# controller_rev2.net
KiCad netlist of a schematic drawn in EAGLE
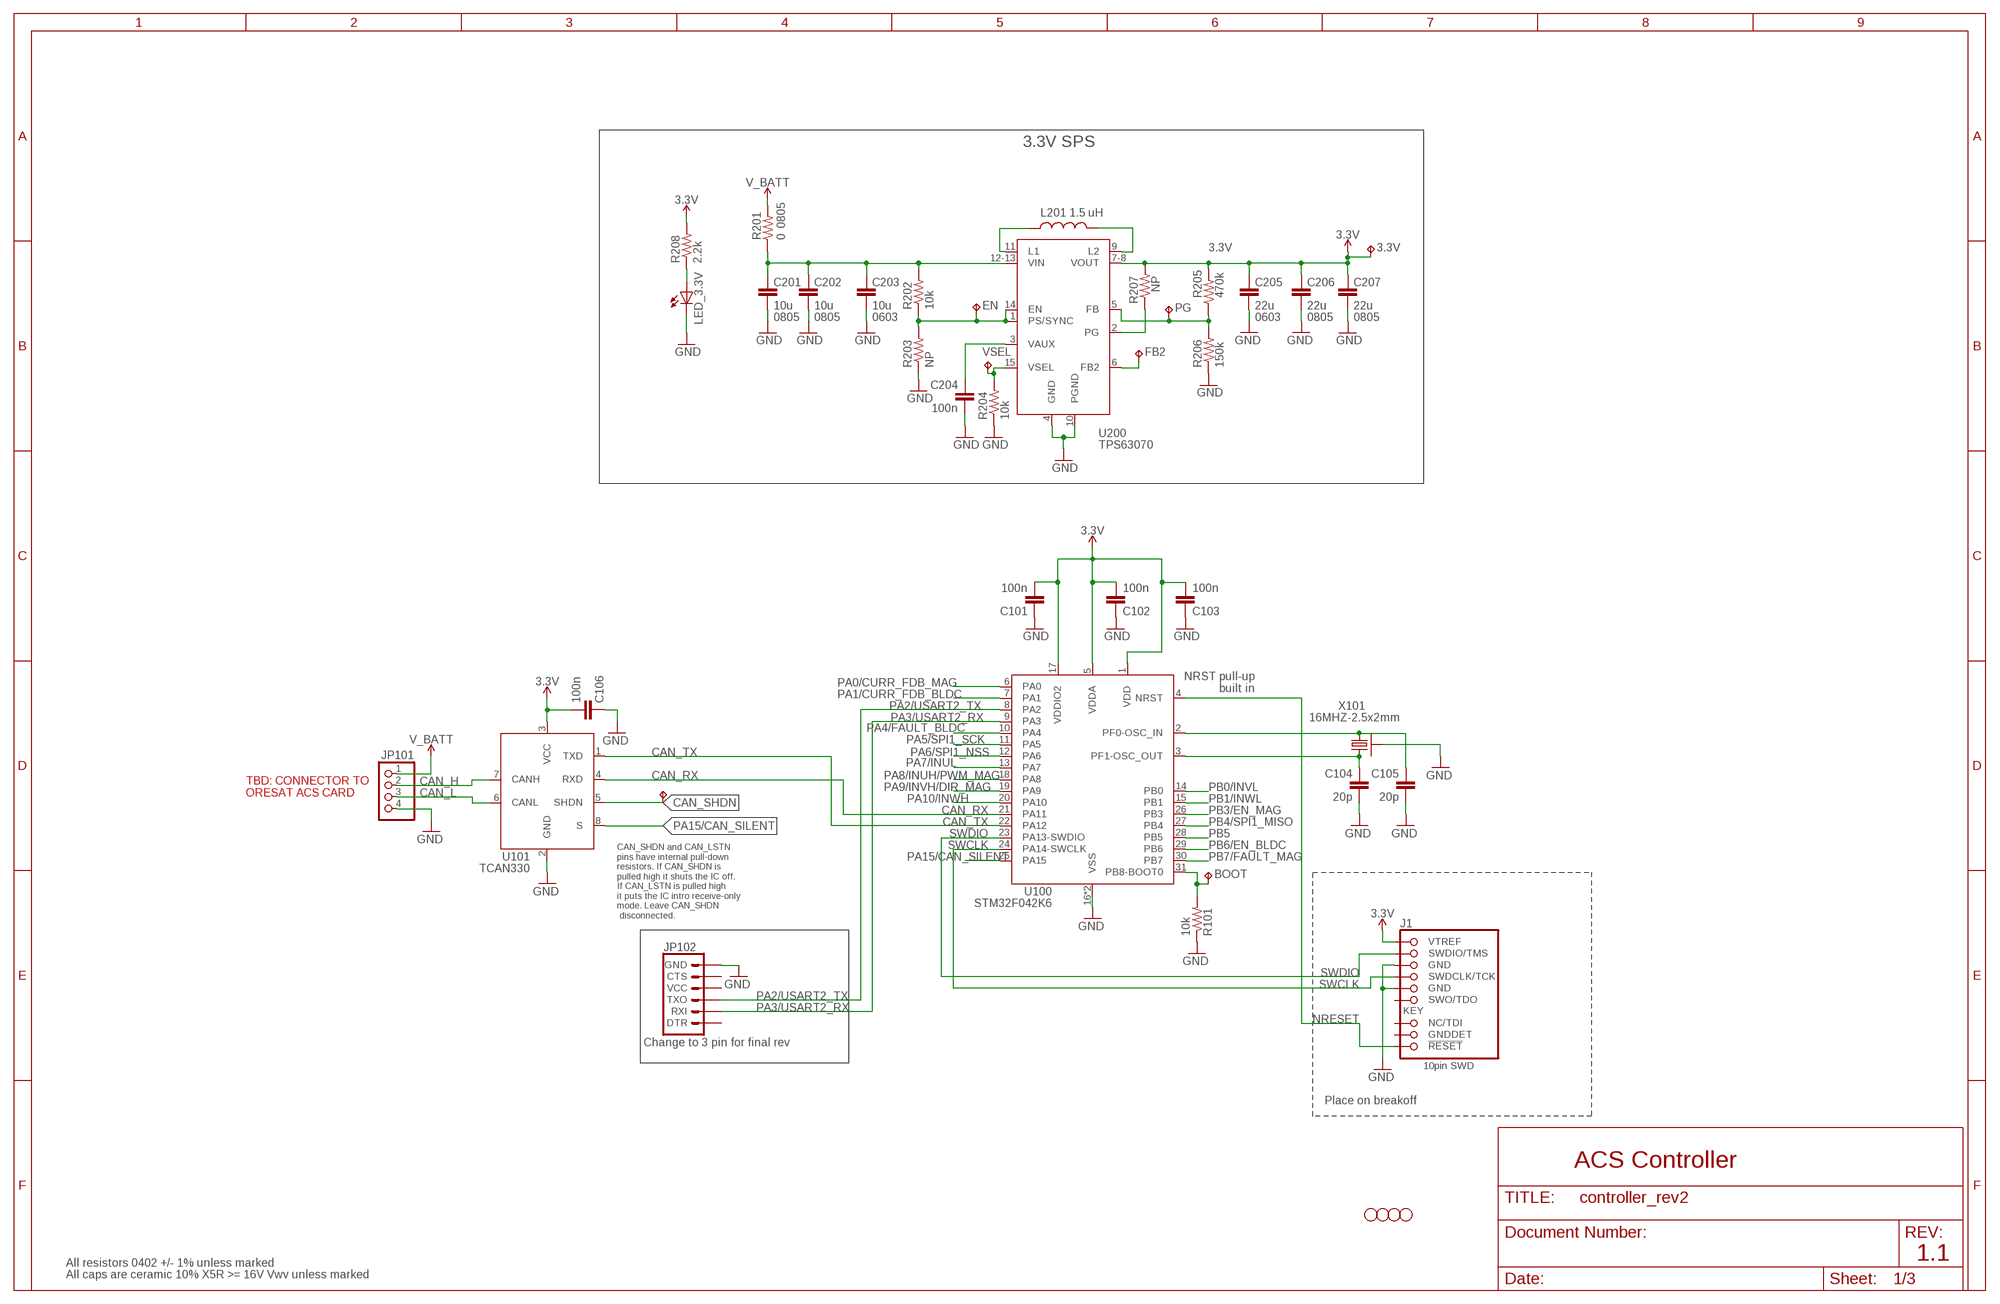
[diagram p0: schematic, sheet 1]
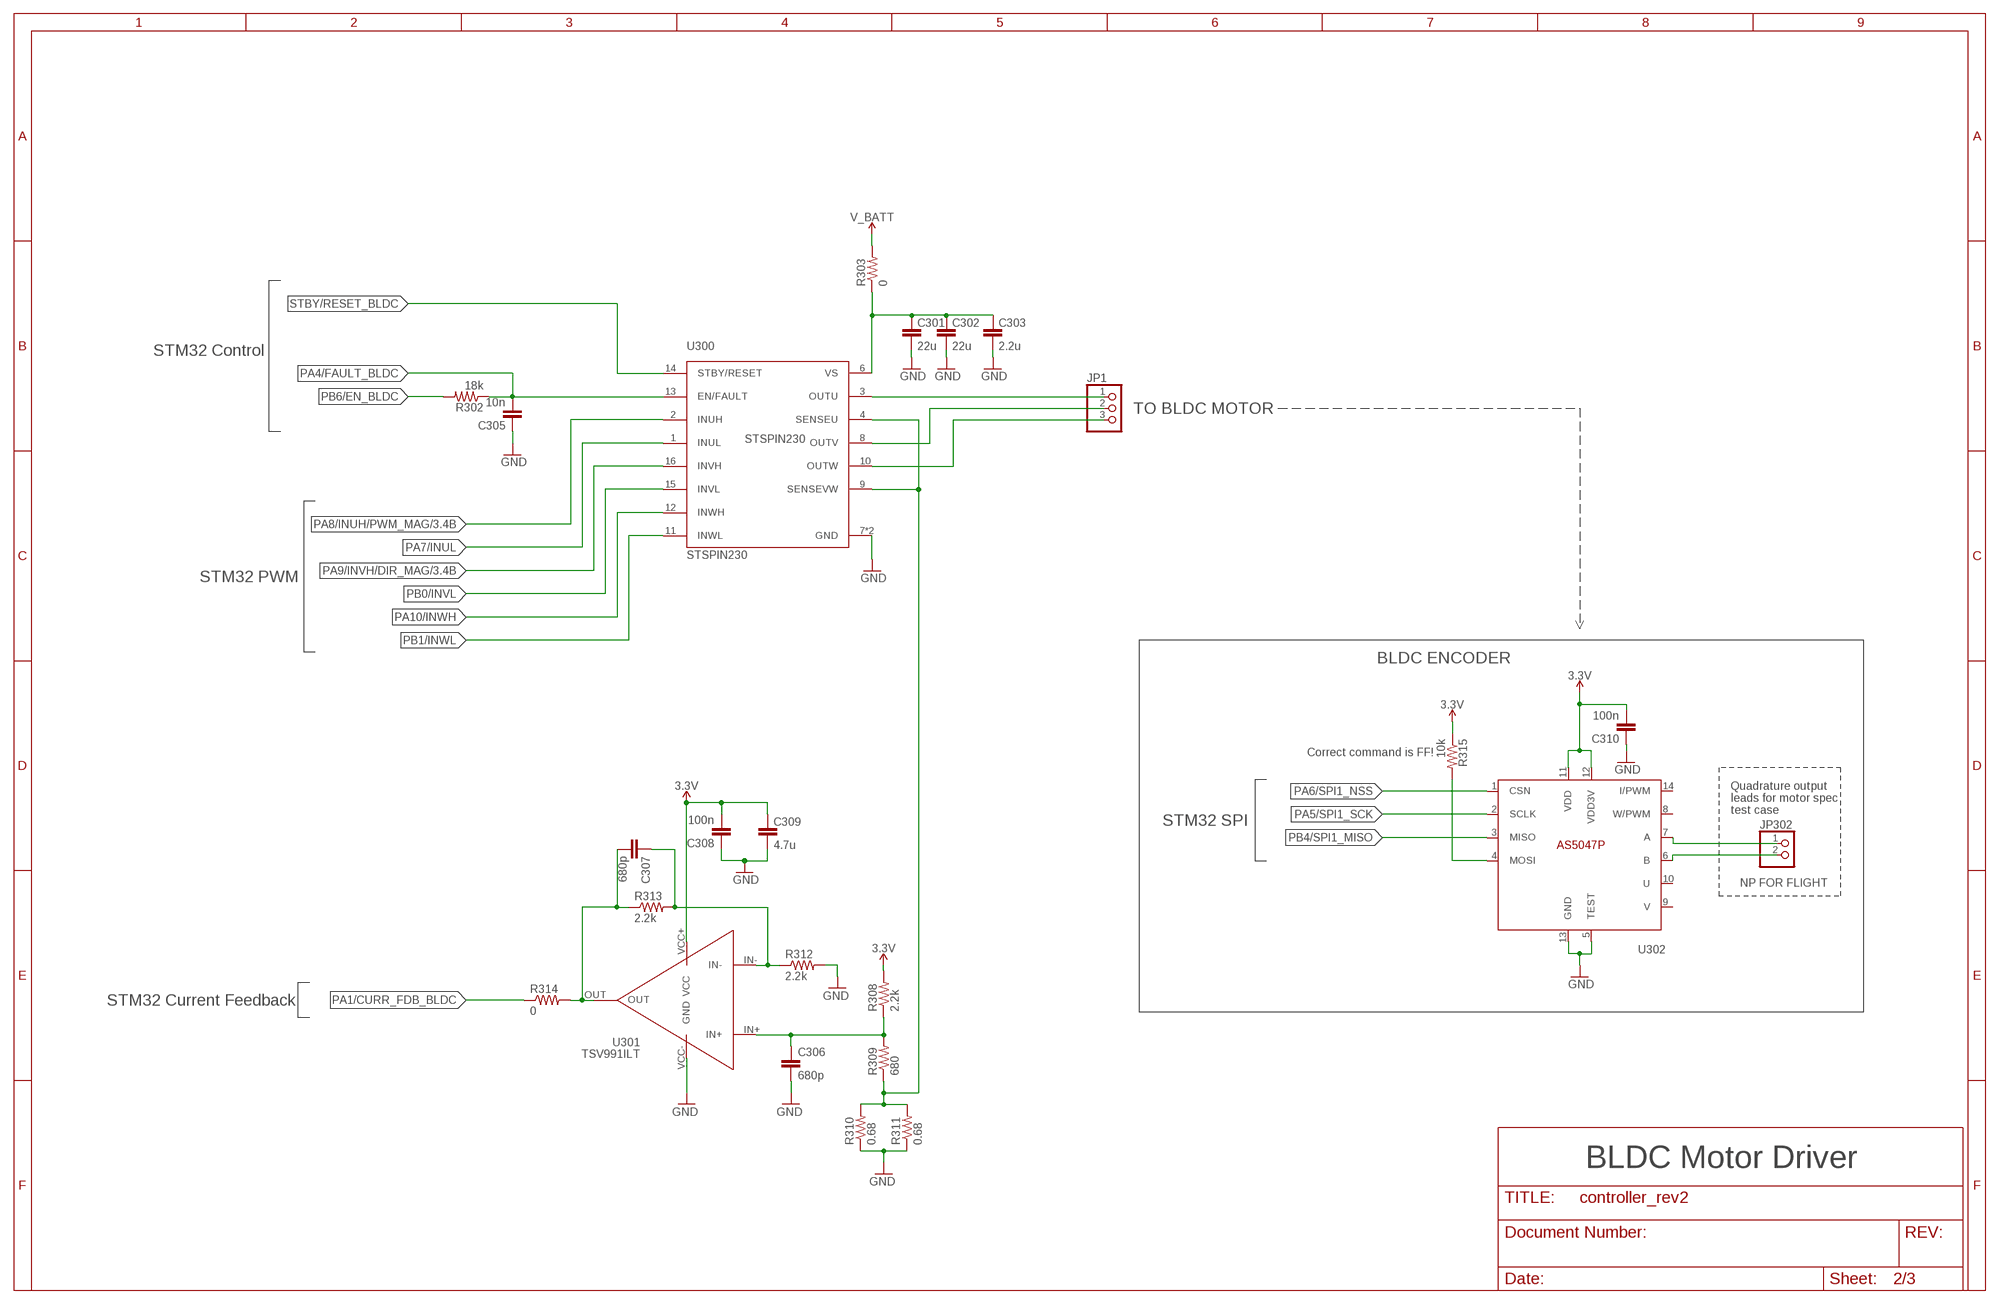
[diagram p1: schematic, sheet 2]
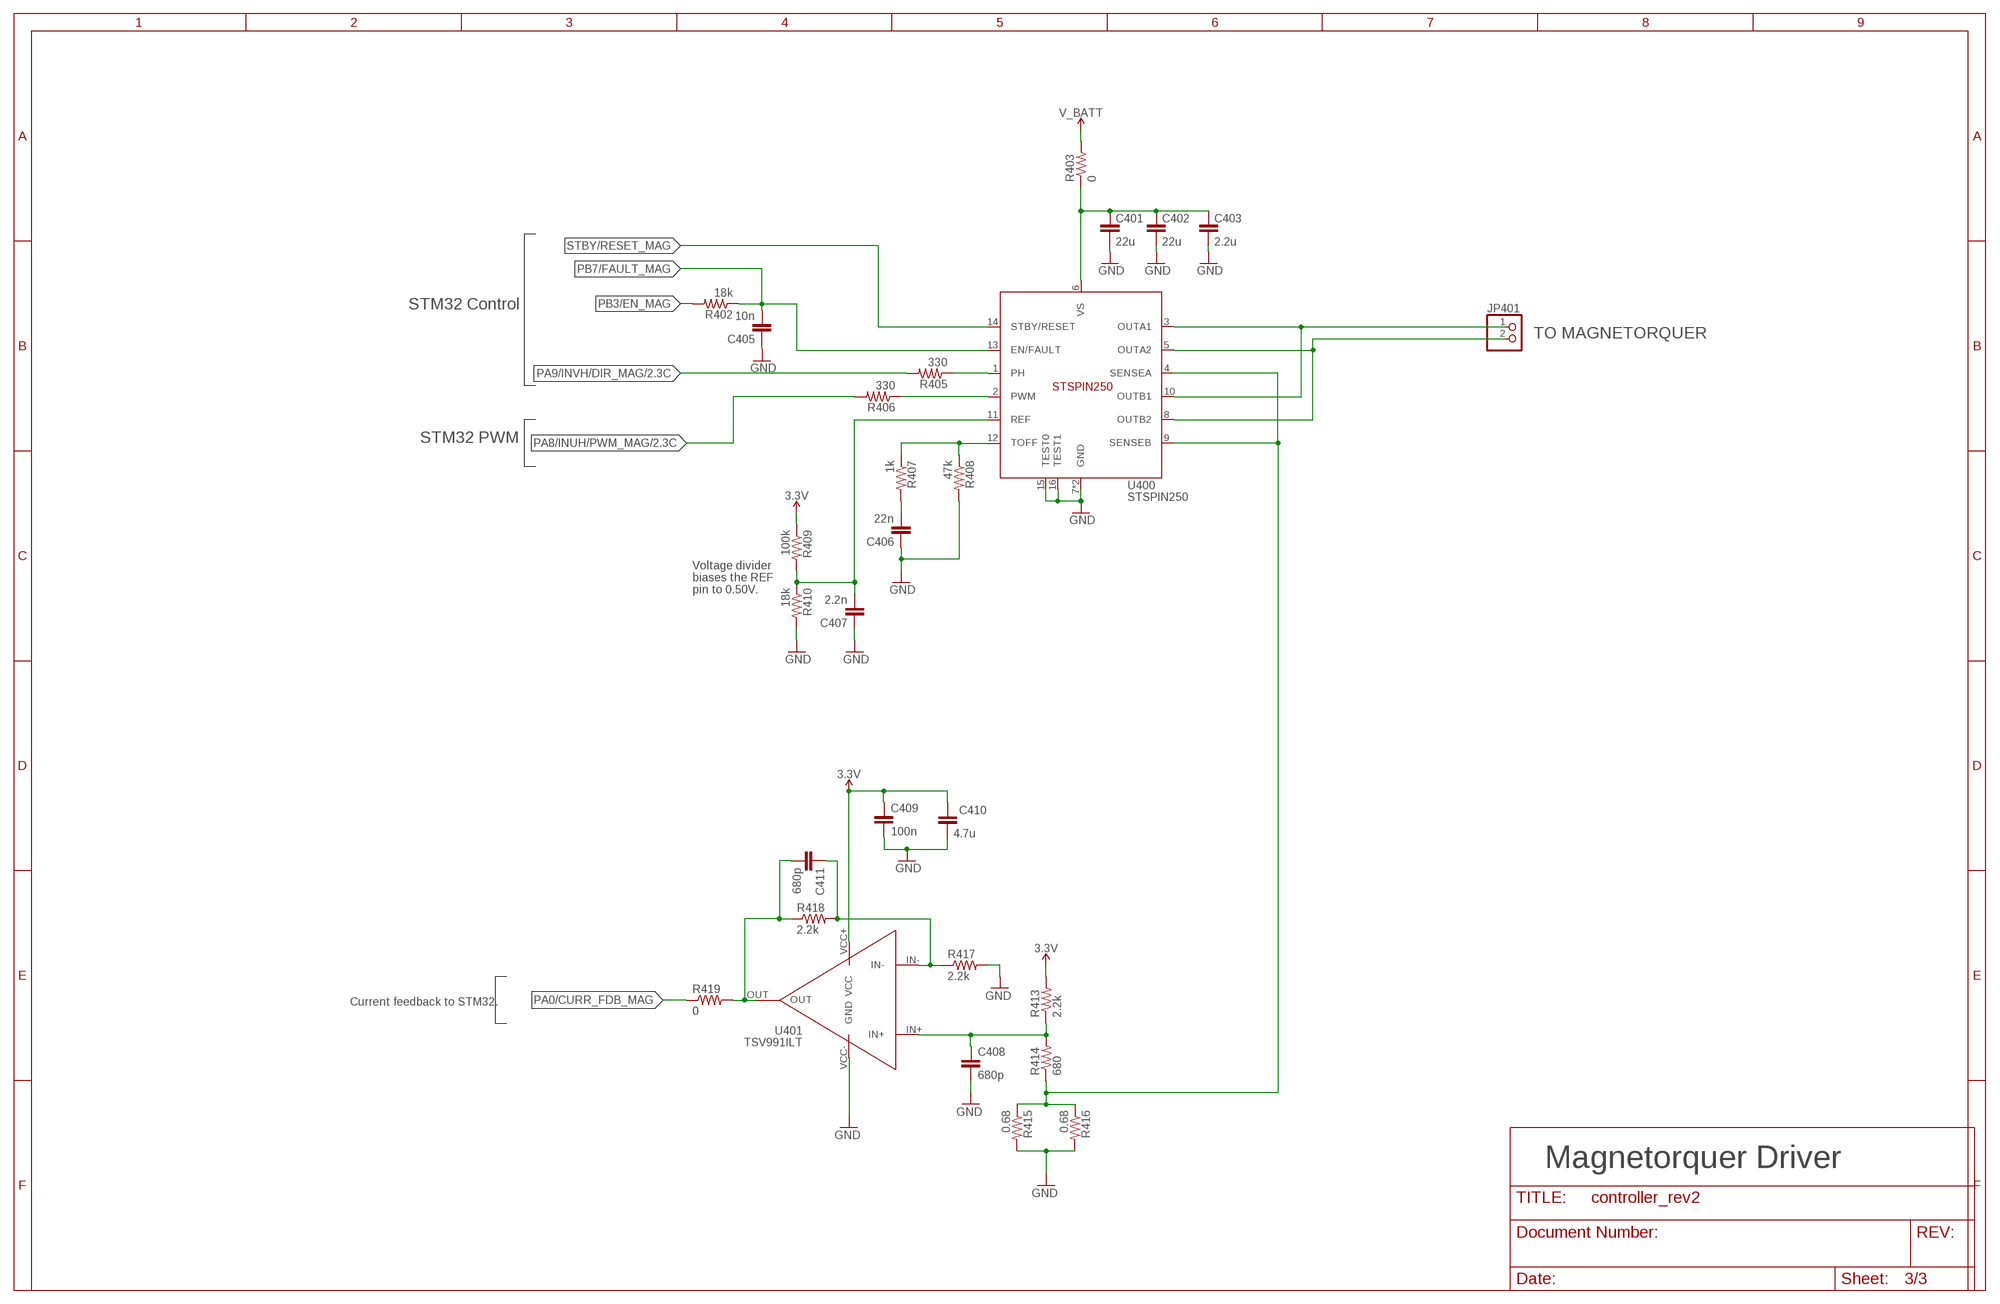
[diagram p2: schematic, sheet 3]

(export (version "E")
  (design (tool "Eeschema 10.0.6"))
  (components
    (comp (ref "C301")
      (value "22u")
      (footprint "eagle-import:.0603-B-NOSILK")
      (fields (field (name "MFR") "Samsung") (field (name "MPN") "CL05B104KO5NNNC"))
      (libsource (lib "eagle-import") (part "C-EU0603-B-NOSILK"))
    )
    (comp (ref "C302")
      (value "22u")
      (footprint "eagle-import:.0603-B-NOSILK")
      (fields (field (name "MFR") "Samsung") (field (name "MPN") "CL05B104KO5NNNC"))
      (libsource (lib "eagle-import") (part "C-EU0603-B-NOSILK"))
    )
    (comp (ref "C303")
      (value "2.2u")
      (footprint "eagle-import:.0603-B-NOSILK")
      (fields (field (name "MFR") "Samsung") (field (name "MPN") "CL05B104KO5NNNC"))
      (libsource (lib "eagle-import") (part "C-EU0603-B-NOSILK"))
    )
    (comp (ref "C305")
      (value "10n")
      (footprint "eagle-import:.0402-B-NOSILK")
      (fields (field (name "MFR") "Samsung") (field (name "MPN") "CL05B104KO5NNNC"))
      (libsource (lib "eagle-import") (part "rcl_custom_C-EU0402-B-NOSILK"))
    )
    (comp (ref "C306")
      (value "680p")
      (footprint "eagle-import:.0402-B-NOSILK")
      (fields (field (name "MFR") "Samsung") (field (name "MPN") "CL05B104KO5NNNC"))
      (libsource (lib "eagle-import") (part "rcl_custom_C-EU0402-B-NOSILK"))
    )
    (comp (ref "C307")
      (value "680p")
      (footprint "eagle-import:.0402-B-NOSILK")
      (fields (field (name "MFR") "Samsung") (field (name "MPN") "CL05B104KO5NNNC"))
      (libsource (lib "eagle-import") (part "rcl_custom_C-EU0402-B-NOSILK"))
    )
    (comp (ref "C308")
      (value "100n")
      (footprint "eagle-import:.0402-B-NOSILK")
      (fields (field (name "MFR") "Samsung") (field (name "MPN") "CL05B104KO5NNNC"))
      (libsource (lib "eagle-import") (part "rcl_custom_C-EU0402-B-NOSILK"))
    )
    (comp (ref "C309")
      (value "4.7u")
      (footprint "eagle-import:.0603-B-NOSILK")
      (fields (field (name "MFR") "Samsung") (field (name "MPN") "CL05B104KO5NNNC"))
      (libsource (lib "eagle-import") (part "C-EU0603-B-NOSILK"))
    )
    (comp (ref "C310")
      (value "100n")
      (footprint "eagle-import:.0402-B-NOSILK")
      (fields (field (name "MFR") "Samsung") (field (name "MPN") "CL05B104KO5NNNC"))
      (libsource (lib "eagle-import") (part "rcl_custom_C-EU0402-B-NOSILK"))
    )
    (comp (ref "JP1")
      (value "PINHD-1X3")
      (footprint "eagle-import:1X03")
      (libsource (lib "eagle-import") (part "PINHD-1X3"))
    )
    (comp (ref "JP302")
      (value "PINHD-1X2")
      (footprint "eagle-import:1X02")
      (libsource (lib "eagle-import") (part "PINHD-1X2"))
    )
    (comp (ref "R302")
      (value "18k")
      (footprint "eagle-import:.0402-B-NOSILK")
      (fields (field (name "MFR") "Samsung") (field (name "MPN") "RC1005F6653CS"))
      (libsource (lib "eagle-import") (part "rcl_custom_R-US_0402-B-NOSILK"))
    )
    (comp (ref "R303")
      (value "0")
      (footprint "eagle-import:.0805-B-NOSILK")
      (libsource (lib "eagle-import") (part "R-US_0805-B-NOSILK"))
    )
    (comp (ref "R308")
      (value "2.2k")
      (footprint "eagle-import:.0402-B-NOSILK")
      (fields (field (name "MFR") "Samsung") (field (name "MPN") "RC1005F6653CS"))
      (libsource (lib "eagle-import") (part "rcl_custom_R-US_0402-B-NOSILK"))
    )
    (comp (ref "R309")
      (value "680")
      (footprint "eagle-import:.0402-B-NOSILK")
      (fields (field (name "MFR") "Samsung") (field (name "MPN") "RC1005F6653CS"))
      (libsource (lib "eagle-import") (part "rcl_custom_R-US_0402-B-NOSILK"))
    )
    (comp (ref "R310")
      (value "0.68")
      (footprint "eagle-import:.0805-B-NOSILK")
      (libsource (lib "eagle-import") (part "R-US_0805-B-NOSILK"))
    )
    (comp (ref "R311")
      (value "0.68")
      (footprint "eagle-import:.0805-B-NOSILK")
      (libsource (lib "eagle-import") (part "R-US_0805-B-NOSILK"))
    )
    (comp (ref "R312")
      (value "2.2k")
      (footprint "eagle-import:.0402-B-NOSILK")
      (fields (field (name "MFR") "Samsung") (field (name "MPN") "RC1005F6653CS"))
      (libsource (lib "eagle-import") (part "rcl_custom_R-US_0402-B-NOSILK"))
    )
    (comp (ref "R313")
      (value "2.2k")
      (footprint "eagle-import:.0402-B-NOSILK")
      (fields (field (name "MFR") "Samsung") (field (name "MPN") "RC1005F6653CS"))
      (libsource (lib "eagle-import") (part "rcl_custom_R-US_0402-B-NOSILK"))
    )
    (comp (ref "R314")
      (value "0")
      (footprint "eagle-import:.0402-B-NOSILK")
      (fields (field (name "MFR") "Samsung") (field (name "MPN") "RC1005F6653CS"))
      (libsource (lib "eagle-import") (part "rcl_custom_R-US_0402-B-NOSILK"))
    )
    (comp (ref "R315")
      (value "10k")
      (footprint "eagle-import:.0402-B-NOSILK")
      (fields (field (name "MFR") "Samsung") (field (name "MPN") "RC1005F6653CS"))
      (libsource (lib "eagle-import") (part "rcl_custom_R-US_0402-B-NOSILK"))
    )
    (comp (ref "U300")
      (value "STSPIN230")
      (footprint "eagle-import:VFQFPN")
      (libsource (lib "eagle-import") (part "STSPIN230"))
    )
    (comp (ref "U301")
      (value "TSV991ILT")
      (footprint "eagle-import:SOT23-5")
      (libsource (lib "eagle-import") (part "TSV991ILT"))
    )
    (comp (ref "U302")
      (value "AS5047P")
      (footprint "eagle-import:TSSOP14")
      (libsource (lib "eagle-import") (part "AS5047P"))
    )
    (comp (ref "3.3V")
      (value "TPTP15SQ")
      (footprint "eagle-import:TP15SQ")
      (libsource (lib "eagle-import") (part "TPTP15SQ"))
    )
    (comp (ref "BOOT")
      (value "TPTP15SQ")
      (footprint "eagle-import:TP15SQ")
      (libsource (lib "eagle-import") (part "TPTP15SQ"))
    )
    (comp (ref "BOOT1")
      (value "TPTP15SQ")
      (footprint "eagle-import:TP15SQ")
      (libsource (lib "eagle-import") (part "TPTP15SQ"))
    )
    (comp (ref "C101")
      (value "100n")
      (footprint "eagle-import:.0402-B-NOSILK")
      (fields (field (name "MFR") "Samsung") (field (name "MPN") "CL05B104KO5NNNC"))
      (libsource (lib "eagle-import") (part "rcl_custom_C-EU0402-B-NOSILK"))
    )
    (comp (ref "C102")
      (value "100n")
      (footprint "eagle-import:.0402-B-NOSILK")
      (fields (field (name "MFR") "Samsung") (field (name "MPN") "CL05B104KO5NNNC"))
      (libsource (lib "eagle-import") (part "rcl_custom_C-EU0402-B-NOSILK"))
    )
    (comp (ref "C103")
      (value "100n")
      (footprint "eagle-import:.0402-B-NOSILK")
      (fields (field (name "MFR") "Samsung") (field (name "MPN") "CL05B104KO5NNNC"))
      (libsource (lib "eagle-import") (part "rcl_custom_C-EU0402-B-NOSILK"))
    )
    (comp (ref "C104")
      (value "20p")
      (footprint "eagle-import:.0402-B-NOSILK")
      (fields (field (name "MFR") "Samsung") (field (name "MPN") "CL05C200JB51PNC"))
      (libsource (lib "eagle-import") (part "rcl_custom_C-EU0402-B-NOSILK"))
    )
    (comp (ref "C105")
      (value "20p")
      (footprint "eagle-import:.0402-B-NOSILK")
      (fields (field (name "MFR") "Samsung") (field (name "MPN") "CL05C200JB51PNC"))
      (libsource (lib "eagle-import") (part "rcl_custom_C-EU0402-B-NOSILK"))
    )
    (comp (ref "C106")
      (value "100n")
      (footprint "eagle-import:.0402-B-NOSILK")
      (fields (field (name "MFR") "Samsung") (field (name "MPN") "CL05B104KO5NNNC"))
      (libsource (lib "eagle-import") (part "rcl_custom_C-EU0402-B-NOSILK"))
    )
    (comp (ref "C201")
      (value "10u")
      (footprint "eagle-import:.0805-B-NOSILK")
      (libsource (lib "eagle-import") (part "C-EU0805-B-NOSILK"))
    )
    (comp (ref "C202")
      (value "10u")
      (footprint "eagle-import:.0805-B-NOSILK")
      (libsource (lib "eagle-import") (part "C-EU0805-B-NOSILK"))
    )
    (comp (ref "C203")
      (value "10u")
      (footprint "eagle-import:.0603-B-NOSILK")
      (fields (field (name "MFR") "Samsung") (field (name "MPN") "CL05B104KO5NNNC"))
      (libsource (lib "eagle-import") (part "C-EU0603-B-NOSILK"))
    )
    (comp (ref "C204")
      (value "100n")
      (footprint "eagle-import:.0402-B-NOSILK")
      (fields (field (name "MFR") "Samsung") (field (name "MPN") "CL05B104KO5NNNC"))
      (libsource (lib "eagle-import") (part "rcl_custom_C-EU0402-B-NOSILK"))
    )
    (comp (ref "C205")
      (value "22u")
      (footprint "eagle-import:.0603-B-NOSILK")
      (fields (field (name "MFR") "Samsung") (field (name "MPN") "CL05B104KO5NNNC"))
      (libsource (lib "eagle-import") (part "C-EU0603-B-NOSILK"))
    )
    (comp (ref "C206")
      (value "22u")
      (footprint "eagle-import:.0805-B-NOSILK")
      (libsource (lib "eagle-import") (part "C-EU0805-B-NOSILK"))
    )
    (comp (ref "C207")
      (value "22u")
      (footprint "eagle-import:.0805-B-NOSILK")
      (libsource (lib "eagle-import") (part "C-EU0805-B-NOSILK"))
    )
    (comp (ref "EN")
      (value "TPTP15SQ")
      (footprint "eagle-import:TP15SQ")
      (libsource (lib "eagle-import") (part "TPTP15SQ"))
    )
    (comp (ref "FB2")
      (value "TPTP15SQ")
      (footprint "eagle-import:TP15SQ")
      (libsource (lib "eagle-import") (part "TPTP15SQ"))
    )
    (comp (ref "H1")
      (value "STAND-OFFTIGHT")
      (footprint "eagle-import:STAND-OFF-TIGHT")
      (libsource (lib "eagle-import") (part "STAND-OFFTIGHT"))
    )
    (comp (ref "H2")
      (value "STAND-OFFTIGHT")
      (footprint "eagle-import:STAND-OFF-TIGHT")
      (libsource (lib "eagle-import") (part "STAND-OFFTIGHT"))
    )
    (comp (ref "H3")
      (value "STAND-OFFTIGHT")
      (footprint "eagle-import:STAND-OFF-TIGHT")
      (libsource (lib "eagle-import") (part "STAND-OFFTIGHT"))
    )
    (comp (ref "H4")
      (value "STAND-OFFTIGHT")
      (footprint "eagle-import:STAND-OFF-TIGHT")
      (libsource (lib "eagle-import") (part "STAND-OFFTIGHT"))
    )
    (comp (ref "J1")
      (value "1.27MM-SWD-CONNECTOR")
      (footprint "eagle-import:1.27MM_2X5")
      (libsource (lib "eagle-import") (part "1.27MM-SWD-CONNECTOR"))
    )
    (comp (ref "JP101")
      (value "PINHD-1X4")
      (footprint "eagle-import:1X04")
      (libsource (lib "eagle-import") (part "PINHD-1X4"))
    )
    (comp (ref "JP102")
      (value "6_PIN_SERIAL_TARGETSILK")
      (footprint "eagle-import:6_PIN_SERIAL_TARGET_SIDE_W_SILK")
      (libsource (lib "eagle-import") (part "6_PIN_SERIAL_TARGETSILK"))
    )
    (comp (ref "L201")
      (value "1.5 uH")
      (footprint "eagle-import:L-COILCRAFT-XFL4020")
      (fields (field (name "MFR") "Coilcraft") (field (name "MPN") "XFL4020-152ME"))
      (libsource (lib "eagle-import") (part "L-COILCRAFT-XFL4020"))
    )
    (comp (ref "LED_3.3V")
      (value "LEDCHIPLED_0603")
      (footprint "eagle-import:CHIPLED_0603")
      (libsource (lib "eagle-import") (part "LEDCHIPLED_0603"))
    )
    (comp (ref "PG")
      (value "TPTP15SQ")
      (footprint "eagle-import:TP15SQ")
      (libsource (lib "eagle-import") (part "TPTP15SQ"))
    )
    (comp (ref "R101")
      (value "10k")
      (footprint "eagle-import:.0402-B-NOSILK")
      (fields (field (name "MFR") "Samsung") (field (name "MPN") "RC1005F6653CS"))
      (libsource (lib "eagle-import") (part "rcl_custom_R-US_0402-B-NOSILK"))
    )
    (comp (ref "R201")
      (value "0")
      (footprint "eagle-import:.0805-B-NOSILK")
      (fields (field (name "MFR") "Rohm") (field (name "MPN") "MCR10EZPJ000"))
      (libsource (lib "eagle-import") (part "rcl_custom_R-US_0805-B-NOSILK"))
    )
    (comp (ref "R202")
      (value "10k")
      (footprint "eagle-import:.0402-B-NOSILK")
      (fields (field (name "MFR") "Samsung") (field (name "MPN") "RC1005F6653CS"))
      (libsource (lib "eagle-import") (part "rcl_custom_R-US_0402-B-NOSILK"))
    )
    (comp (ref "R203")
      (value "NP")
      (footprint "eagle-import:.0402-B-NOSILK")
      (fields (field (name "MFR") "Samsung") (field (name "MPN") "RC1005F6653CS"))
      (libsource (lib "eagle-import") (part "rcl_custom_R-US_0402-B-NOSILK"))
    )
    (comp (ref "R204")
      (value "10k")
      (footprint "eagle-import:.0402-B-NOSILK")
      (fields (field (name "MFR") "Samsung") (field (name "MPN") "RC1005F6653CS"))
      (libsource (lib "eagle-import") (part "rcl_custom_R-US_0402-B-NOSILK"))
    )
    (comp (ref "R205")
      (value "470k")
      (footprint "eagle-import:.0402-B-NOSILK")
      (fields (field (name "MFR") "Samsung") (field (name "MPN") "RC1005F6653CS"))
      (libsource (lib "eagle-import") (part "rcl_custom_R-US_0402-B-NOSILK"))
    )
    (comp (ref "R206")
      (value "150k")
      (footprint "eagle-import:.0402-B-NOSILK")
      (fields (field (name "MFR") "Samsung") (field (name "MPN") "RC1005F6653CS"))
      (libsource (lib "eagle-import") (part "rcl_custom_R-US_0402-B-NOSILK"))
    )
    (comp (ref "R207")
      (value "NP")
      (footprint "eagle-import:.0402-B-NOSILK")
      (fields (field (name "MFR") "Samsung") (field (name "MPN") "RC1005F6653CS"))
      (libsource (lib "eagle-import") (part "rcl_custom_R-US_0402-B-NOSILK"))
    )
    (comp (ref "R208")
      (value "2.2k")
      (footprint "eagle-import:.0603-B-NOSILK")
      (libsource (lib "eagle-import") (part "R-US_0603-B-NOSILK"))
    )
    (comp (ref "U100")
      (value "STM32F042K6")
      (footprint "eagle-import:QFP32-7X7")
      (fields (field (name "MFR") "STMicroelectronics") (field (name "MPN") "STM32F042K6T7"))
      (libsource (lib "eagle-import") (part "STM32F042K6"))
    )
    (comp (ref "U101")
      (value "TCAN330")
      (footprint "eagle-import:SOT23-8_TI-DCN")
      (fields (field (name "MFR") "Texas Instruments") (field (name "MPN") "TCAN330GDCNT"))
      (libsource (lib "eagle-import") (part "TCAN330"))
    )
    (comp (ref "U200")
      (value "TPS63070")
      (footprint "eagle-import:TPS63070X")
      (libsource (lib "eagle-import") (part "TPS63070X"))
    )
    (comp (ref "VSEL")
      (value "TPTP15SQ")
      (footprint "eagle-import:TP15SQ")
      (libsource (lib "eagle-import") (part "TPTP15SQ"))
    )
    (comp (ref "X101")
      (value "16MHZ-2.5x2mm")
      (footprint "eagle-import:CRYSTAL_2.5X2")
      (fields (field (name "MFR") "ECS Inc.") (field (name "MPN") "ECS-160-10-36Q-ES-TR"))
      (libsource (lib "eagle-import") (part "CRYSTAL-WITH-GND"))
    )
    (comp (ref "C401")
      (value "22u")
      (footprint "eagle-import:.0603-B-NOSILK")
      (fields (field (name "MFR") "Samsung") (field (name "MPN") "CL05B104KO5NNNC"))
      (libsource (lib "eagle-import") (part "C-EU0603-B-NOSILK"))
    )
    (comp (ref "C402")
      (value "22u")
      (footprint "eagle-import:.0603-B-NOSILK")
      (fields (field (name "MFR") "Samsung") (field (name "MPN") "CL05B104KO5NNNC"))
      (libsource (lib "eagle-import") (part "C-EU0603-B-NOSILK"))
    )
    (comp (ref "C403")
      (value "2.2u")
      (footprint "eagle-import:.0603-B-NOSILK")
      (fields (field (name "MFR") "Samsung") (field (name "MPN") "CL05B104KO5NNNC"))
      (libsource (lib "eagle-import") (part "C-EU0603-B-NOSILK"))
    )
    (comp (ref "C405")
      (value "10n")
      (footprint "eagle-import:.0402-B-NOSILK")
      (fields (field (name "MFR") "Samsung") (field (name "MPN") "CL05B104KO5NNNC"))
      (libsource (lib "eagle-import") (part "rcl_custom_C-EU0402-B-NOSILK"))
    )
    (comp (ref "C406")
      (value "22n")
      (footprint "eagle-import:.0402-B-NOSILK")
      (fields (field (name "MFR") "Samsung") (field (name "MPN") "CL05B104KO5NNNC"))
      (libsource (lib "eagle-import") (part "rcl_custom_C-EU0402-B-NOSILK"))
    )
    (comp (ref "C407")
      (value "2.2n")
      (footprint "eagle-import:.0402-B-NOSILK")
      (fields (field (name "MFR") "Samsung") (field (name "MPN") "CL05B104KO5NNNC"))
      (libsource (lib "eagle-import") (part "rcl_custom_C-EU0402-B-NOSILK"))
    )
    (comp (ref "C408")
      (value "680p")
      (footprint "eagle-import:.0402-B-NOSILK")
      (fields (field (name "MFR") "Samsung") (field (name "MPN") "CL05B104KO5NNNC"))
      (libsource (lib "eagle-import") (part "rcl_custom_C-EU0402-B-NOSILK"))
    )
    (comp (ref "C409")
      (value "100n")
      (footprint "eagle-import:.0402-B-NOSILK")
      (fields (field (name "MFR") "Samsung") (field (name "MPN") "CL05B104KO5NNNC"))
      (libsource (lib "eagle-import") (part "rcl_custom_C-EU0402-B-NOSILK"))
    )
    (comp (ref "C410")
      (value "4.7u")
      (footprint "eagle-import:.0603-B-NOSILK")
      (fields (field (name "MFR") "Samsung") (field (name "MPN") "CL05B104KO5NNNC"))
      (libsource (lib "eagle-import") (part "C-EU0603-B-NOSILK"))
    )
    (comp (ref "C411")
      (value "680p")
      (footprint "eagle-import:.0402-B-NOSILK")
      (fields (field (name "MFR") "Samsung") (field (name "MPN") "CL05B104KO5NNNC"))
      (libsource (lib "eagle-import") (part "rcl_custom_C-EU0402-B-NOSILK"))
    )
    (comp (ref "JP401")
      (value "PINHD-1X2")
      (footprint "eagle-import:1X02")
      (libsource (lib "eagle-import") (part "PINHD-1X2"))
    )
    (comp (ref "R402")
      (value "18k")
      (footprint "eagle-import:.0402-B-NOSILK")
      (fields (field (name "MFR") "Samsung") (field (name "MPN") "RC1005F6653CS"))
      (libsource (lib "eagle-import") (part "rcl_custom_R-US_0402-B-NOSILK"))
    )
    (comp (ref "R403")
      (value "0")
      (footprint "eagle-import:.0805-B-NOSILK")
      (libsource (lib "eagle-import") (part "R-US_0805-B-NOSILK"))
    )
    (comp (ref "R405")
      (value "330")
      (footprint "eagle-import:.0402-B-NOSILK")
      (fields (field (name "MFR") "Samsung") (field (name "MPN") "RC1005F6653CS"))
      (libsource (lib "eagle-import") (part "rcl_custom_R-US_0402-B-NOSILK"))
    )
    (comp (ref "R406")
      (value "330")
      (footprint "eagle-import:.0402-B-NOSILK")
      (fields (field (name "MFR") "Samsung") (field (name "MPN") "RC1005F6653CS"))
      (libsource (lib "eagle-import") (part "rcl_custom_R-US_0402-B-NOSILK"))
    )
    (comp (ref "R407")
      (value "1k")
      (footprint "eagle-import:.0402-B-NOSILK")
      (fields (field (name "MFR") "Samsung") (field (name "MPN") "RC1005F6653CS"))
      (libsource (lib "eagle-import") (part "rcl_custom_R-US_0402-B-NOSILK"))
    )
    (comp (ref "R408")
      (value "47k")
      (footprint "eagle-import:.0402-B-NOSILK")
      (fields (field (name "MFR") "Samsung") (field (name "MPN") "RC1005F6653CS"))
      (libsource (lib "eagle-import") (part "rcl_custom_R-US_0402-B-NOSILK"))
    )
    (comp (ref "R409")
      (value "100k")
      (footprint "eagle-import:.0402-B-NOSILK")
      (fields (field (name "MFR") "Samsung") (field (name "MPN") "RC1005F6653CS"))
      (libsource (lib "eagle-import") (part "rcl_custom_R-US_0402-B-NOSILK"))
    )
    (comp (ref "R410")
      (value "18k")
      (footprint "eagle-import:.0402-B-NOSILK")
      (fields (field (name "MFR") "Samsung") (field (name "MPN") "RC1005F6653CS"))
      (libsource (lib "eagle-import") (part "rcl_custom_R-US_0402-B-NOSILK"))
    )
    (comp (ref "R413")
      (value "2.2k")
      (footprint "eagle-import:.0402-B-NOSILK")
      (fields (field (name "MFR") "Samsung") (field (name "MPN") "RC1005F6653CS"))
      (libsource (lib "eagle-import") (part "rcl_custom_R-US_0402-B-NOSILK"))
    )
    (comp (ref "R414")
      (value "680")
      (footprint "eagle-import:.0402-B-NOSILK")
      (fields (field (name "MFR") "Samsung") (field (name "MPN") "RC1005F6653CS"))
      (libsource (lib "eagle-import") (part "rcl_custom_R-US_0402-B-NOSILK"))
    )
    (comp (ref "R415")
      (value "0.68")
      (footprint "eagle-import:.0805-B-NOSILK")
      (libsource (lib "eagle-import") (part "R-US_0805-B-NOSILK"))
    )
    (comp (ref "R416")
      (value "0.68")
      (footprint "eagle-import:.0805-B-NOSILK")
      (libsource (lib "eagle-import") (part "R-US_0805-B-NOSILK"))
    )
    (comp (ref "R417")
      (value "2.2k")
      (footprint "eagle-import:.0402-B-NOSILK")
      (fields (field (name "MFR") "Samsung") (field (name "MPN") "RC1005F6653CS"))
      (libsource (lib "eagle-import") (part "rcl_custom_R-US_0402-B-NOSILK"))
    )
    (comp (ref "R418")
      (value "2.2k")
      (footprint "eagle-import:.0402-B-NOSILK")
      (fields (field (name "MFR") "Samsung") (field (name "MPN") "RC1005F6653CS"))
      (libsource (lib "eagle-import") (part "rcl_custom_R-US_0402-B-NOSILK"))
    )
    (comp (ref "R419")
      (value "0")
      (footprint "eagle-import:.0402-B-NOSILK")
      (fields (field (name "MFR") "Samsung") (field (name "MPN") "RC1005F6653CS"))
      (libsource (lib "eagle-import") (part "rcl_custom_R-US_0402-B-NOSILK"))
    )
    (comp (ref "U400")
      (value "STSPIN250")
      (footprint "eagle-import:VFQPN")
      (libsource (lib "eagle-import") (part "STSPIN250"))
    )
    (comp (ref "U401")
      (value "TSV991ILT")
      (footprint "eagle-import:SOT23-5")
      (libsource (lib "eagle-import") (part "TSV991ILT"))
    )
  )
  (nets
    (net (code "1") (name "3.3V") (class "Default")
      (node (ref "3.3V") (pin "TP") (pinfunction "TP_TP") (pintype "input"))
      (node (ref "C101") (pin "2") (pinfunction "2_2") (pintype "passive"))
      (node (ref "C102") (pin "2") (pinfunction "2_2") (pintype "passive"))
      (node (ref "C103") (pin "2") (pinfunction "2_2") (pintype "passive"))
      (node (ref "C106") (pin "2") (pinfunction "2_2") (pintype "passive"))
      (node (ref "C205") (pin "1") (pinfunction "1_1") (pintype "passive"))
      (node (ref "C206") (pin "1") (pinfunction "1_1") (pintype "passive"))
      (node (ref "C207") (pin "1") (pinfunction "1_1") (pintype "passive"))
      (node (ref "C308") (pin "2") (pinfunction "2_2") (pintype "passive"))
      (node (ref "C309") (pin "1") (pinfunction "1_1") (pintype "passive"))
      (node (ref "C310") (pin "2") (pinfunction "2_2") (pintype "passive"))
      (node (ref "C409") (pin "1") (pinfunction "1_1") (pintype "passive"))
      (node (ref "C410") (pin "1") (pinfunction "1_1") (pintype "passive"))
      (node (ref "J1") (pin "VTREF") (pinfunction "VTREF_VTREF") (pintype "passive"))
      (node (ref "R205") (pin "2") (pinfunction "2_2") (pintype "passive"))
      (node (ref "R207") (pin "2") (pinfunction "2_2") (pintype "passive"))
      (node (ref "R208") (pin "2") (pinfunction "2_2") (pintype "passive"))
      (node (ref "R308") (pin "2") (pinfunction "2_2") (pintype "passive"))
      (node (ref "R315") (pin "1") (pinfunction "1_1") (pintype "passive"))
      (node (ref "R409") (pin "1") (pinfunction "1_1") (pintype "passive"))
      (node (ref "R413") (pin "2") (pinfunction "2_2") (pintype "passive"))
      (node (ref "U100") (pin "1") (pinfunction "VDD_1") (pintype "power_in"))
      (node (ref "U100") (pin "17") (pinfunction "VDDIO2_17") (pintype "power_in"))
      (node (ref "U100") (pin "5") (pinfunction "VDDA_5") (pintype "power_in"))
      (node (ref "U101") (pin "3") (pinfunction "VCC_3") (pintype "power_in"))
      (node (ref "U200") (pin "7-8") (pinfunction "VOUT_7-8") (pintype "power_in"))
      (node (ref "U301") (pin "VCC+") (pinfunction "VCC_VCC+") (pintype "bidirectional"))
      (node (ref "U302") (pin "11") (pinfunction "VDD_11") (pintype "power_in"))
      (node (ref "U302") (pin "12") (pinfunction "VDD3V_12") (pintype "power_in"))
      (node (ref "U401") (pin "VCC+") (pinfunction "VCC_VCC+") (pintype "bidirectional"))
    )
    (net (code "2") (name "CAN_H") (class "Default")
      (node (ref "JP101") (pin "2") (pinfunction "2_2") (pintype "passive"))
      (node (ref "U101") (pin "7") (pinfunction "CANH_7") (pintype "bidirectional"))
    )
    (net (code "3") (name "CAN_L") (class "Default")
      (node (ref "JP101") (pin "3") (pinfunction "3_3") (pintype "passive"))
      (node (ref "U101") (pin "6") (pinfunction "CANL_6") (pintype "bidirectional"))
    )
    (net (code "4") (name "CAN_RX") (class "Default")
      (node (ref "U100") (pin "21") (pinfunction "PA11_21") (pintype "bidirectional"))
      (node (ref "U101") (pin "4") (pinfunction "RXD_4") (pintype "output"))
    )
    (net (code "5") (name "CAN_SHDN") (class "Default")
      (node (ref "BOOT1") (pin "TP") (pinfunction "TP_TP") (pintype "input"))
      (node (ref "U101") (pin "5") (pinfunction "SHDN_5") (pintype "input"))
    )
    (net (code "6") (name "CAN_TX") (class "Default")
      (node (ref "U100") (pin "22") (pinfunction "PA12_22") (pintype "bidirectional"))
      (node (ref "U101") (pin "1") (pinfunction "TXD_1") (pintype "input"))
    )
    (net (code "7") (name "GND") (class "Default")
      (node (ref "C101") (pin "1") (pinfunction "1_1") (pintype "passive"))
      (node (ref "C102") (pin "1") (pinfunction "1_1") (pintype "passive"))
      (node (ref "C103") (pin "1") (pinfunction "1_1") (pintype "passive"))
      (node (ref "C104") (pin "2") (pinfunction "2_2") (pintype "passive"))
      (node (ref "C105") (pin "2") (pinfunction "2_2") (pintype "passive"))
      (node (ref "C106") (pin "1") (pinfunction "1_1") (pintype "passive"))
      (node (ref "C201") (pin "2") (pinfunction "2_2") (pintype "passive"))
      (node (ref "C202") (pin "2") (pinfunction "2_2") (pintype "passive"))
      (node (ref "C203") (pin "2") (pinfunction "2_2") (pintype "passive"))
      (node (ref "C204") (pin "2") (pinfunction "2_2") (pintype "passive"))
      (node (ref "C205") (pin "2") (pinfunction "2_2") (pintype "passive"))
      (node (ref "C206") (pin "2") (pinfunction "2_2") (pintype "passive"))
      (node (ref "C207") (pin "2") (pinfunction "2_2") (pintype "passive"))
      (node (ref "C301") (pin "2") (pinfunction "2_2") (pintype "passive"))
      (node (ref "C302") (pin "2") (pinfunction "2_2") (pintype "passive"))
      (node (ref "C303") (pin "2") (pinfunction "2_2") (pintype "passive"))
      (node (ref "C305") (pin "1") (pinfunction "1_1") (pintype "passive"))
      (node (ref "C306") (pin "2") (pinfunction "2_2") (pintype "passive"))
      (node (ref "C308") (pin "1") (pinfunction "1_1") (pintype "passive"))
      (node (ref "C309") (pin "2") (pinfunction "2_2") (pintype "passive"))
      (node (ref "C310") (pin "1") (pinfunction "1_1") (pintype "passive"))
      (node (ref "C401") (pin "2") (pinfunction "2_2") (pintype "passive"))
      (node (ref "C402") (pin "2") (pinfunction "2_2") (pintype "passive"))
      (node (ref "C403") (pin "2") (pinfunction "2_2") (pintype "passive"))
      (node (ref "C405") (pin "1") (pinfunction "1_1") (pintype "passive"))
      (node (ref "C406") (pin "1") (pinfunction "1_1") (pintype "passive"))
      (node (ref "C407") (pin "1") (pinfunction "1_1") (pintype "passive"))
      (node (ref "C408") (pin "2") (pinfunction "2_2") (pintype "passive"))
      (node (ref "C409") (pin "2") (pinfunction "2_2") (pintype "passive"))
      (node (ref "C410") (pin "2") (pinfunction "2_2") (pintype "passive"))
      (node (ref "J1") (pin "GND") (pinfunction "GND_GND") (pintype "passive"))
      (node (ref "J1") (pin "GND@2") (pinfunction "GND_GND@2") (pintype "passive"))
      (node (ref "JP101") (pin "4") (pinfunction "4_4") (pintype "passive"))
      (node (ref "JP102") (pin "P$6") (pinfunction "GND_P$6") (pintype "passive"))
      (node (ref "LED_3.3V") (pin "C") (pinfunction "C_C") (pintype "passive"))
      (node (ref "R101") (pin "1") (pinfunction "1_1") (pintype "passive"))
      (node (ref "R203") (pin "1") (pinfunction "1_1") (pintype "passive"))
      (node (ref "R204") (pin "1") (pinfunction "1_1") (pintype "passive"))
      (node (ref "R206") (pin "1") (pinfunction "1_1") (pintype "passive"))
      (node (ref "R310") (pin "1") (pinfunction "1_1") (pintype "passive"))
      (node (ref "R311") (pin "1") (pinfunction "1_1") (pintype "passive"))
      (node (ref "R312") (pin "2") (pinfunction "2_2") (pintype "passive"))
      (node (ref "R408") (pin "2") (pinfunction "2_2") (pintype "passive"))
      (node (ref "R410") (pin "2") (pinfunction "2_2") (pintype "passive"))
      (node (ref "R415") (pin "2") (pinfunction "2_2") (pintype "passive"))
      (node (ref "R416") (pin "2") (pinfunction "2_2") (pintype "passive"))
      (node (ref "R417") (pin "2") (pinfunction "2_2") (pintype "passive"))
      (node (ref "U100") (pin "16") (pinfunction "VSS_16") (pintype "power_in"))
      (node (ref "U100") (pin "32") (pinfunction "VSS_32") (pintype "power_in"))
      (node (ref "U101") (pin "2") (pinfunction "GND_2") (pintype "power_in"))
      (node (ref "U200") (pin "10") (pinfunction "PGND_10") (pintype "power_in"))
      (node (ref "U200") (pin "4") (pinfunction "GND_4") (pintype "power_in"))
      (node (ref "U300") (pin "7") (pinfunction "GND_7") (pintype "power_in"))
      (node (ref "U300") (pin "EPAD") (pinfunction "GND_EPAD") (pintype "power_in"))
      (node (ref "U301") (pin "VCC-") (pinfunction "GND_VCC-") (pintype "bidirectional"))
      (node (ref "U302") (pin "13") (pinfunction "GND_13") (pintype "power_in"))
      (node (ref "U302") (pin "5") (pinfunction "TEST_5") (pintype "power_in"))
      (node (ref "U400") (pin "15") (pinfunction "TEST0_15") (pintype "bidirectional"))
      (node (ref "U400") (pin "16") (pinfunction "TEST1_16") (pintype "bidirectional"))
      (node (ref "U400") (pin "7") (pinfunction "GND_7") (pintype "power_in"))
      (node (ref "U400") (pin "EPAD") (pinfunction "GND_EPAD") (pintype "power_in"))
      (node (ref "U401") (pin "VCC-") (pinfunction "GND_VCC-") (pintype "bidirectional"))
      (node (ref "X101") (pin "2") (pinfunction "SHIELD_2") (pintype "power_in"))
      (node (ref "X101") (pin "4") (pinfunction "SHIELD_4") (pintype "power_in"))
    )
    (net (code "8") (name "NRESET") (class "Default")
      (node (ref "J1") (pin "!RESET") (pinfunction "~{RESET}_!RESET") (pintype "passive"))
      (node (ref "U100") (pin "4") (pinfunction "NRST_4") (pintype "bidirectional"))
    )
    (net (code "9") (name "Net-(C306-Pad1)") (class "Default")
      (node (ref "C306") (pin "1") (pinfunction "1_1") (pintype "passive"))
      (node (ref "R308") (pin "1") (pinfunction "1_1") (pintype "passive"))
      (node (ref "R309") (pin "2") (pinfunction "2_2") (pintype "passive"))
      (node (ref "U301") (pin "IN+") (pinfunction "IN+_IN+") (pintype "bidirectional"))
    )
    (net (code "10") (name "Net-(C307-Pad1)") (class "Default")
      (node (ref "C307") (pin "1") (pinfunction "1_1") (pintype "passive"))
      (node (ref "R312") (pin "1") (pinfunction "1_1") (pintype "passive"))
      (node (ref "R313") (pin "2") (pinfunction "2_2") (pintype "passive"))
      (node (ref "U301") (pin "IN-") (pinfunction "IN-_IN-") (pintype "bidirectional"))
    )
    (net (code "11") (name "Net-(C307-Pad2)") (class "Default")
      (node (ref "C307") (pin "2") (pinfunction "2_2") (pintype "passive"))
      (node (ref "R313") (pin "1") (pinfunction "1_1") (pintype "passive"))
      (node (ref "R314") (pin "2") (pinfunction "2_2") (pintype "passive"))
      (node (ref "U301") (pin "OUT") (pinfunction "OUT_OUT") (pintype "bidirectional"))
    )
    (net (code "12") (name "Net-(C406-Pad2)") (class "Default")
      (node (ref "C406") (pin "2") (pinfunction "2_2") (pintype "passive"))
      (node (ref "R407") (pin "2") (pinfunction "2_2") (pintype "passive"))
    )
    (net (code "13") (name "Net-(C408-Pad1)") (class "Default")
      (node (ref "C408") (pin "1") (pinfunction "1_1") (pintype "passive"))
      (node (ref "R413") (pin "1") (pinfunction "1_1") (pintype "passive"))
      (node (ref "R414") (pin "2") (pinfunction "2_2") (pintype "passive"))
      (node (ref "U401") (pin "IN+") (pinfunction "IN+_IN+") (pintype "bidirectional"))
    )
    (net (code "14") (name "Net-(C411-Pad1)") (class "Default")
      (node (ref "C411") (pin "1") (pinfunction "1_1") (pintype "passive"))
      (node (ref "R417") (pin "1") (pinfunction "1_1") (pintype "passive"))
      (node (ref "R418") (pin "2") (pinfunction "2_2") (pintype "passive"))
      (node (ref "U401") (pin "IN-") (pinfunction "IN-_IN-") (pintype "bidirectional"))
    )
    (net (code "15") (name "Net-(C411-Pad2)") (class "Default")
      (node (ref "C411") (pin "2") (pinfunction "2_2") (pintype "passive"))
      (node (ref "R418") (pin "1") (pinfunction "1_1") (pintype "passive"))
      (node (ref "R419") (pin "2") (pinfunction "2_2") (pintype "passive"))
      (node (ref "U401") (pin "OUT") (pinfunction "OUT_OUT") (pintype "bidirectional"))
    )
    (net (code "16") (name "Net-(LED_3.3V-PadA)") (class "Default")
      (node (ref "LED_3.3V") (pin "A") (pinfunction "A_A") (pintype "passive"))
      (node (ref "R208") (pin "1") (pinfunction "1_1") (pintype "passive"))
    )
    (net (code "17") (name "Net-(U100-PB8-BOOT0)") (class "Default")
      (node (ref "BOOT") (pin "TP") (pinfunction "TP_TP") (pintype "input"))
      (node (ref "R101") (pin "2") (pinfunction "2_2") (pintype "passive"))
      (node (ref "U100") (pin "31") (pinfunction "PB8-BOOT0_31") (pintype "bidirectional"))
    )
    (net (code "18") (name "Net-(U100-PF0-OSC_IN)") (class "Default")
      (node (ref "C105") (pin "1") (pinfunction "1_1") (pintype "passive"))
      (node (ref "U100") (pin "2") (pinfunction "PF0-OSC_IN_2") (pintype "bidirectional"))
      (node (ref "X101") (pin "1") (pinfunction "1_1") (pintype "passive"))
    )
    (net (code "19") (name "Net-(U100-PF1-OSC_OUT)") (class "Default")
      (node (ref "C104") (pin "1") (pinfunction "1_1") (pintype "passive"))
      (node (ref "U100") (pin "3") (pinfunction "PF1-OSC_OUT_3") (pintype "bidirectional"))
      (node (ref "X101") (pin "3") (pinfunction "2_3") (pintype "passive"))
    )
    (net (code "20") (name "Net-(U200-EN)") (class "Default")
      (node (ref "EN") (pin "TP") (pinfunction "TP_TP") (pintype "input"))
      (node (ref "R202") (pin "1") (pinfunction "1_1") (pintype "passive"))
      (node (ref "R203") (pin "2") (pinfunction "2_2") (pintype "passive"))
      (node (ref "U200") (pin "1") (pinfunction "PS/SYNC_1") (pintype "input"))
      (node (ref "U200") (pin "14") (pinfunction "EN_14") (pintype "input"))
    )
    (net (code "21") (name "Net-(U200-FB)") (class "Default")
      (node (ref "PG") (pin "TP") (pinfunction "TP_TP") (pintype "input"))
      (node (ref "R205") (pin "1") (pinfunction "1_1") (pintype "passive"))
      (node (ref "R206") (pin "2") (pinfunction "2_2") (pintype "passive"))
      (node (ref "U200") (pin "5") (pinfunction "FB_5") (pintype "passive"))
    )
    (net (code "22") (name "Net-(U200-FB2)") (class "Default")
      (node (ref "FB2") (pin "TP") (pinfunction "TP_TP") (pintype "input"))
      (node (ref "U200") (pin "6") (pinfunction "FB2_6") (pintype "passive"))
    )
    (net (code "23") (name "Net-(U200-L1)") (class "Default")
      (node (ref "L201") (pin "1") (pinfunction "1_1") (pintype "passive"))
      (node (ref "U200") (pin "11") (pinfunction "L1_11") (pintype "passive"))
    )
    (net (code "24") (name "Net-(U200-L2)") (class "Default")
      (node (ref "L201") (pin "2") (pinfunction "2_2") (pintype "passive"))
      (node (ref "U200") (pin "9") (pinfunction "L2_9") (pintype "passive"))
    )
    (net (code "25") (name "Net-(U200-PG)") (class "Default")
      (node (ref "R207") (pin "1") (pinfunction "1_1") (pintype "passive"))
      (node (ref "U200") (pin "2") (pinfunction "PG_2") (pintype "open_collector"))
    )
    (net (code "26") (name "Net-(U200-VAUX)") (class "Default")
      (node (ref "C204") (pin "1") (pinfunction "1_1") (pintype "passive"))
      (node (ref "U200") (pin "3") (pinfunction "VAUX_3") (pintype "output"))
    )
    (net (code "27") (name "Net-(U200-VIN)") (class "Default")
      (node (ref "C201") (pin "1") (pinfunction "1_1") (pintype "passive"))
      (node (ref "C202") (pin "1") (pinfunction "1_1") (pintype "passive"))
      (node (ref "C203") (pin "1") (pinfunction "1_1") (pintype "passive"))
      (node (ref "R201") (pin "1") (pinfunction "1_1") (pintype "passive"))
      (node (ref "R202") (pin "2") (pinfunction "2_2") (pintype "passive"))
      (node (ref "U200") (pin "12-13") (pinfunction "VIN_12-13") (pintype "power_in"))
    )
    (net (code "28") (name "Net-(U200-VSEL)") (class "Default")
      (node (ref "R204") (pin "2") (pinfunction "2_2") (pintype "passive"))
      (node (ref "U200") (pin "15") (pinfunction "VSEL_15") (pintype "input"))
      (node (ref "VSEL") (pin "TP") (pinfunction "TP_TP") (pintype "input"))
    )
    (net (code "29") (name "Net-(U300-OUTU)") (class "Default")
      (node (ref "JP1") (pin "1") (pinfunction "1_1") (pintype "passive"))
      (node (ref "U300") (pin "3") (pinfunction "OUTU_3") (pintype "output"))
    )
    (net (code "30") (name "Net-(U300-OUTV)") (class "Default")
      (node (ref "JP1") (pin "2") (pinfunction "2_2") (pintype "passive"))
      (node (ref "U300") (pin "8") (pinfunction "OUTV_8") (pintype "output"))
    )
    (net (code "31") (name "Net-(U300-OUTW)") (class "Default")
      (node (ref "JP1") (pin "3") (pinfunction "3_3") (pintype "passive"))
      (node (ref "U300") (pin "10") (pinfunction "OUTW_10") (pintype "output"))
    )
    (net (code "32") (name "Net-(U300-SENSEU)") (class "Default")
      (node (ref "R309") (pin "1") (pinfunction "1_1") (pintype "passive"))
      (node (ref "R310") (pin "2") (pinfunction "2_2") (pintype "passive"))
      (node (ref "R311") (pin "2") (pinfunction "2_2") (pintype "passive"))
      (node (ref "U300") (pin "4") (pinfunction "SENSEU_4") (pintype "output"))
      (node (ref "U300") (pin "9") (pinfunction "SENSEVW_9") (pintype "output"))
    )
    (net (code "33") (name "Net-(U300-VS)") (class "Default")
      (node (ref "C301") (pin "1") (pinfunction "1_1") (pintype "passive"))
      (node (ref "C302") (pin "1") (pinfunction "1_1") (pintype "passive"))
      (node (ref "C303") (pin "1") (pinfunction "1_1") (pintype "passive"))
      (node (ref "R303") (pin "1") (pinfunction "1_1") (pintype "passive"))
      (node (ref "U300") (pin "6") (pinfunction "VS_6") (pintype "power_in"))
    )
    (net (code "34") (name "Net-(U302-A)") (class "Default")
      (node (ref "JP302") (pin "1") (pinfunction "1_1") (pintype "passive"))
      (node (ref "U302") (pin "7") (pinfunction "A_7") (pintype "output"))
    )
    (net (code "35") (name "Net-(U302-B)") (class "Default")
      (node (ref "JP302") (pin "2") (pinfunction "2_2") (pintype "passive"))
      (node (ref "U302") (pin "6") (pinfunction "B_6") (pintype "output"))
    )
    (net (code "36") (name "Net-(U302-MOSI)") (class "Default")
      (node (ref "R315") (pin "2") (pinfunction "2_2") (pintype "passive"))
      (node (ref "U302") (pin "4") (pinfunction "MOSI_4") (pintype "input"))
    )
    (net (code "37") (name "Net-(U400-OUTA1)") (class "Default")
      (node (ref "JP401") (pin "1") (pinfunction "1_1") (pintype "passive"))
      (node (ref "U400") (pin "10") (pinfunction "OUTB1_10") (pintype "output"))
      (node (ref "U400") (pin "3") (pinfunction "OUTA1_3") (pintype "output"))
    )
    (net (code "38") (name "Net-(U400-OUTA2)") (class "Default")
      (node (ref "JP401") (pin "2") (pinfunction "2_2") (pintype "passive"))
      (node (ref "U400") (pin "5") (pinfunction "OUTA2_5") (pintype "output"))
      (node (ref "U400") (pin "8") (pinfunction "OUTB2_8") (pintype "output"))
    )
    (net (code "39") (name "Net-(U400-PH)") (class "Default")
      (node (ref "R405") (pin "1") (pinfunction "1_1") (pintype "passive"))
      (node (ref "U400") (pin "1") (pinfunction "PH_1") (pintype "input"))
    )
    (net (code "40") (name "Net-(U400-PWM)") (class "Default")
      (node (ref "R406") (pin "1") (pinfunction "1_1") (pintype "passive"))
      (node (ref "U400") (pin "2") (pinfunction "PWM_2") (pintype "input"))
    )
    (net (code "41") (name "Net-(U400-REF)") (class "Default")
      (node (ref "C407") (pin "2") (pinfunction "2_2") (pintype "passive"))
      (node (ref "R409") (pin "2") (pinfunction "2_2") (pintype "passive"))
      (node (ref "R410") (pin "1") (pinfunction "1_1") (pintype "passive"))
      (node (ref "U400") (pin "11") (pinfunction "REF_11") (pintype "passive"))
    )
    (net (code "42") (name "Net-(U400-SENSEA)") (class "Default")
      (node (ref "R414") (pin "1") (pinfunction "1_1") (pintype "passive"))
      (node (ref "R415") (pin "1") (pinfunction "1_1") (pintype "passive"))
      (node (ref "R416") (pin "1") (pinfunction "1_1") (pintype "passive"))
      (node (ref "U400") (pin "4") (pinfunction "SENSEA_4") (pintype "output"))
      (node (ref "U400") (pin "9") (pinfunction "SENSEB_9") (pintype "output"))
    )
    (net (code "43") (name "Net-(U400-TOFF)") (class "Default")
      (node (ref "R407") (pin "1") (pinfunction "1_1") (pintype "passive"))
      (node (ref "R408") (pin "1") (pinfunction "1_1") (pintype "passive"))
      (node (ref "U400") (pin "12") (pinfunction "TOFF_12") (pintype "passive"))
    )
    (net (code "44") (name "Net-(U400-VS)") (class "Default")
      (node (ref "C401") (pin "1") (pinfunction "1_1") (pintype "passive"))
      (node (ref "C402") (pin "1") (pinfunction "1_1") (pintype "passive"))
      (node (ref "C403") (pin "1") (pinfunction "1_1") (pintype "passive"))
      (node (ref "R403") (pin "1") (pinfunction "1_1") (pintype "passive"))
      (node (ref "U400") (pin "6") (pinfunction "VS_6") (pintype "power_in"))
    )
    (net (code "45") (name "PA0{slash}CURR_FDB_MAG") (class "Default")
      (node (ref "R419") (pin "1") (pinfunction "1_1") (pintype "passive"))
      (node (ref "U100") (pin "6") (pinfunction "PA0_6") (pintype "bidirectional"))
    )
    (net (code "46") (name "PA1{slash}CURR_FDB_BLDC") (class "Default")
      (node (ref "R314") (pin "1") (pinfunction "1_1") (pintype "passive"))
      (node (ref "U100") (pin "7") (pinfunction "PA1_7") (pintype "bidirectional"))
    )
    (net (code "47") (name "PA2{slash}USART2_TX") (class "Default")
      (node (ref "JP102") (pin "P$2") (pinfunction "TXO_P$2") (pintype "passive"))
      (node (ref "U100") (pin "8") (pinfunction "PA2_8") (pintype "bidirectional"))
    )
    (net (code "48") (name "PA3{slash}USART2_RX") (class "Default")
      (node (ref "JP102") (pin "P$3") (pinfunction "RXI_P$3") (pintype "passive"))
      (node (ref "U100") (pin "9") (pinfunction "PA3_9") (pintype "bidirectional"))
    )
    (net (code "49") (name "PA4{slash}FAULT_BLDC") (class "Default")
      (node (ref "C305") (pin "2") (pinfunction "2_2") (pintype "passive"))
      (node (ref "R302") (pin "1") (pinfunction "1_1") (pintype "passive"))
      (node (ref "U100") (pin "10") (pinfunction "PA4_10") (pintype "bidirectional"))
      (node (ref "U300") (pin "13") (pinfunction "EN/FAULT_13") (pintype "bidirectional"))
    )
    (net (code "50") (name "PA5{slash}SPI1_SCK") (class "Default")
      (node (ref "U100") (pin "11") (pinfunction "PA5_11") (pintype "bidirectional"))
      (node (ref "U302") (pin "2") (pinfunction "SCLK_2") (pintype "input"))
    )
    (net (code "51") (name "PA6{slash}SPI1_NSS") (class "Default")
      (node (ref "U100") (pin "12") (pinfunction "PA6_12") (pintype "bidirectional"))
      (node (ref "U302") (pin "1") (pinfunction "CSN_1") (pintype "input"))
    )
    (net (code "52") (name "PA7{slash}INUL") (class "Default")
      (node (ref "U100") (pin "13") (pinfunction "PA7_13") (pintype "bidirectional"))
      (node (ref "U300") (pin "1") (pinfunction "INUL_1") (pintype "input"))
    )
    (net (code "53") (name "PA8{slash}INUH{slash}PWM_MAG") (class "Default")
      (node (ref "R406") (pin "2") (pinfunction "2_2") (pintype "passive"))
      (node (ref "U100") (pin "18") (pinfunction "PA8_18") (pintype "bidirectional"))
      (node (ref "U300") (pin "2") (pinfunction "INUH_2") (pintype "input"))
    )
    (net (code "54") (name "PA9{slash}INVH{slash}DIR_MAG") (class "Default")
      (node (ref "R405") (pin "2") (pinfunction "2_2") (pintype "passive"))
      (node (ref "U100") (pin "19") (pinfunction "PA9_19") (pintype "bidirectional"))
      (node (ref "U300") (pin "16") (pinfunction "INVH_16") (pintype "input"))
    )
    (net (code "55") (name "PA10{slash}INWH") (class "Default")
      (node (ref "U100") (pin "20") (pinfunction "PA10_20") (pintype "bidirectional"))
      (node (ref "U300") (pin "12") (pinfunction "INWH_12") (pintype "input"))
    )
    (net (code "56") (name "PA15{slash}CAN_SILENT") (class "Default")
      (node (ref "U100") (pin "25") (pinfunction "PA15_25") (pintype "bidirectional"))
      (node (ref "U101") (pin "8") (pinfunction "S_8") (pintype "input"))
    )
    (net (code "57") (name "PB0{slash}INVL") (class "Default")
      (node (ref "U100") (pin "14") (pinfunction "PB0_14") (pintype "bidirectional"))
      (node (ref "U300") (pin "15") (pinfunction "INVL_15") (pintype "input"))
    )
    (net (code "58") (name "PB1{slash}INWL") (class "Default")
      (node (ref "U100") (pin "15") (pinfunction "PB1_15") (pintype "bidirectional"))
      (node (ref "U300") (pin "11") (pinfunction "INWL_11") (pintype "input"))
    )
    (net (code "59") (name "PB3{slash}EN_MAG") (class "Default")
      (node (ref "R402") (pin "2") (pinfunction "2_2") (pintype "passive"))
      (node (ref "U100") (pin "26") (pinfunction "PB3_26") (pintype "bidirectional"))
    )
    (net (code "60") (name "PB4{slash}SPI1_MISO") (class "Default")
      (node (ref "U100") (pin "27") (pinfunction "PB4_27") (pintype "bidirectional"))
      (node (ref "U302") (pin "3") (pinfunction "MISO_3") (pintype "output"))
    )
    (net (code "61") (name "PB5") (class "Default")
      (node (ref "U100") (pin "28") (pinfunction "PB5_28") (pintype "bidirectional"))
    )
    (net (code "62") (name "PB6{slash}EN_BLDC") (class "Default")
      (node (ref "R302") (pin "2") (pinfunction "2_2") (pintype "passive"))
      (node (ref "U100") (pin "29") (pinfunction "PB6_29") (pintype "bidirectional"))
    )
    (net (code "63") (name "PB7{slash}FAULT_MAG") (class "Default")
      (node (ref "C405") (pin "2") (pinfunction "2_2") (pintype "passive"))
      (node (ref "R402") (pin "1") (pinfunction "1_1") (pintype "passive"))
      (node (ref "U100") (pin "30") (pinfunction "PB7_30") (pintype "bidirectional"))
      (node (ref "U400") (pin "13") (pinfunction "EN/FAULT_13") (pintype "bidirectional"))
    )
    (net (code "64") (name "STBY{slash}RESET_BLDC") (class "Default")
      (node (ref "U300") (pin "14") (pinfunction "STBY/RESET_14") (pintype "input"))
    )
    (net (code "65") (name "STBY{slash}RESET_MAG") (class "Default")
      (node (ref "U400") (pin "14") (pinfunction "STBY/RESET_14") (pintype "bidirectional"))
    )
    (net (code "66") (name "SWCLK") (class "Default")
      (node (ref "J1") (pin "SWDCLK") (pinfunction "SWDCLK/TCK_SWDCLK") (pintype "passive"))
      (node (ref "U100") (pin "24") (pinfunction "PA14-SWCLK_24") (pintype "bidirectional"))
    )
    (net (code "67") (name "SWDIO") (class "Default")
      (node (ref "J1") (pin "SWDIO") (pinfunction "SWDIO/TMS_SWDIO") (pintype "passive"))
      (node (ref "U100") (pin "23") (pinfunction "PA13-SWDIO_23") (pintype "bidirectional"))
    )
    (net (code "68") (name "V_BATT") (class "Default")
      (node (ref "JP101") (pin "1") (pinfunction "1_1") (pintype "passive"))
      (node (ref "R201") (pin "2") (pinfunction "2_2") (pintype "passive"))
      (node (ref "R303") (pin "2") (pinfunction "2_2") (pintype "passive"))
      (node (ref "R403") (pin "2") (pinfunction "2_2") (pintype "passive"))
    )
    (net (code "69") (name "unconnected-(J1-NC{slash}TDI-PadNC)") (class "Default")
      (node (ref "J1") (pin "NC") (pinfunction "NC/TDI_NC") (pintype "passive"))
    )
    (net (code "70") (name "unconnected-(J1-PadGNDDET)") (class "Default")
      (node (ref "J1") (pin "GNDDET") (pinfunction "GNDDET_GNDDET") (pintype "passive"))
    )
    (net (code "71") (name "unconnected-(J1-SWO{slash}TDO-PadSWO)") (class "Default")
      (node (ref "J1") (pin "SWO") (pinfunction "SWO/TDO_SWO") (pintype "passive"))
    )
    (net (code "72") (name "unconnected-(JP102-CTS-PadP$5)") (class "Default")
      (node (ref "JP102") (pin "P$5") (pinfunction "CTS_P$5") (pintype "passive"))
    )
    (net (code "73") (name "unconnected-(JP102-DTR-PadP$1)") (class "Default")
      (node (ref "JP102") (pin "P$1") (pinfunction "DTR_P$1") (pintype "passive"))
    )
    (net (code "74") (name "unconnected-(JP102-VCC-PadP$4)") (class "Default")
      (node (ref "JP102") (pin "P$4") (pinfunction "VCC_P$4") (pintype "passive"))
    )
    (net (code "75") (name "unconnected-(U302-I{slash}PWM-Pad14)") (class "Default")
      (node (ref "U302") (pin "14") (pinfunction "I/PWM_14") (pintype "output"))
    )
    (net (code "76") (name "unconnected-(U302-U-Pad10)") (class "Default")
      (node (ref "U302") (pin "10") (pinfunction "U_10") (pintype "output"))
    )
    (net (code "77") (name "unconnected-(U302-V-Pad9)") (class "Default")
      (node (ref "U302") (pin "9") (pinfunction "V_9") (pintype "output"))
    )
    (net (code "78") (name "unconnected-(U302-W{slash}PWM-Pad8)") (class "Default")
      (node (ref "U302") (pin "8") (pinfunction "W/PWM_8") (pintype "output"))
    )
  )
)
